# UPCNSL-ABS-PVC-2B.net
KiCad netlist of a schematic drawn in Altium Designer
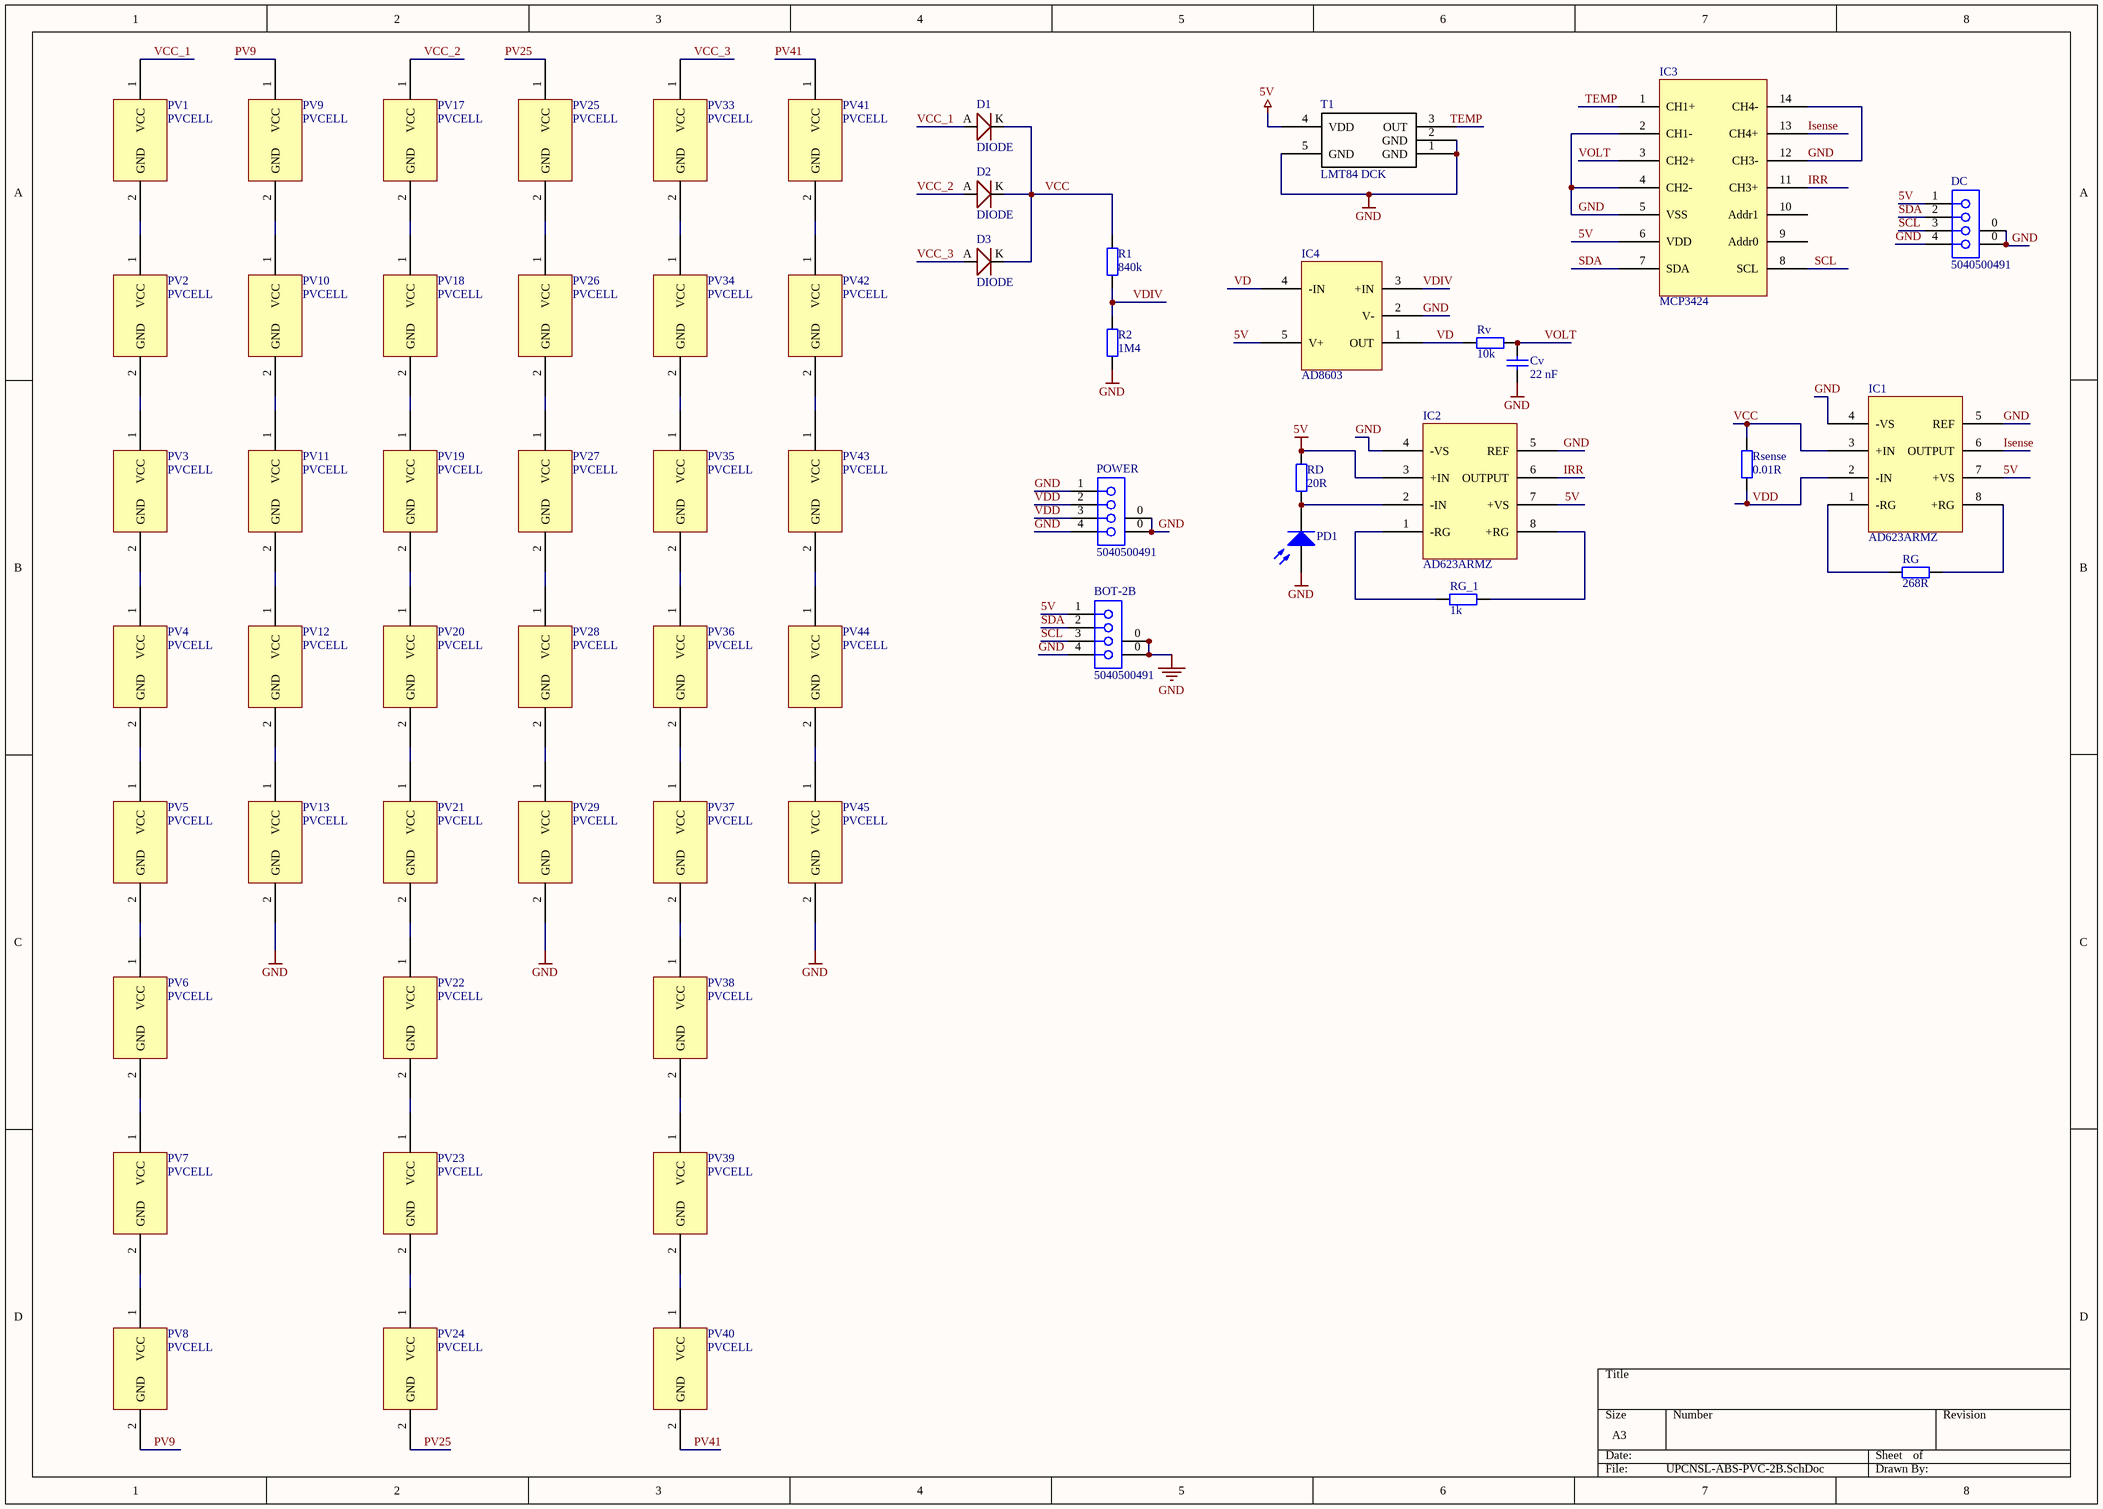
[diagram p0: UPCNSL-ABS-PVC-2B.SchDoc]

(export (version "E")
  (design (tool "Eeschema 10.0.6"))
  (components
    (comp (ref "BOT-2B")
      (value "5040500491")
      (footprint "5040500491")
      (libsource (lib "3CAT_Connectors") (part "MOLEX_5040500491"))
    )
    (comp (ref "Cv")
      (value "22 nF")
      (footprint "CAP0603")
      (description "Capacitor")
      (fields (field (name "Comment") "CAP0603"))
      (libsource (lib "UPCNSL-ABS-FLS-ARD_v1.2") (part "CAP0603"))
    )
    (comp (ref "D1")
      (value "DIODE")
      (footprint "(Schottky diode) SODFL160X70-2N")
      (libsource (lib "UPCNSL-ABS-FLS-ARD_v1.2") (part "DIODE"))
    )
    (comp (ref "D2")
      (value "DIODE")
      (footprint "(Schottky diode) SODFL160X70-2N")
      (libsource (lib "UPCNSL-ABS-FLS-ARD_v1.2") (part "DIODE"))
    )
    (comp (ref "D3")
      (value "DIODE")
      (footprint "(Schottky diode) SODFL160X70-2N")
      (libsource (lib "UPCNSL-ABS-FLS-ARD_v1.2") (part "DIODE"))
    )
    (comp (ref "DC")
      (value "5040500491")
      (footprint "5040500491")
      (libsource (lib "3CAT_Connectors") (part "MOLEX_5040500491"))
    )
    (comp (ref "IC1")
      (value "AD623ARMZ")
      (footprint "AD623ARMZ")
      (libsource (lib "UPCNSL-ABS-FLS-PVC") (part "AD623ARMZ"))
    )
    (comp (ref "IC2")
      (value "AD623ARMZ")
      (footprint "AD623ARMZ")
      (libsource (lib "UPCNSL-ABS-FLS-PVC") (part "AD623ARMZ"))
    )
    (comp (ref "IC3")
      (value "MCP3424")
      (footprint "MCP3424")
      (description "18-Bit, Multi-Channel ΔΣ Analog-to-Digital Converter with  I2C")
      (libsource (lib "UPCNSL-ABS-FLS-PVC") (part "MCP3424"))
    )
    (comp (ref "IC4")
      (value "AD8603")
      (footprint "AD8603")
      (libsource (lib "UPCNSL-ABS-FLS-PVC") (part "AD8603"))
    )
    (comp (ref "PD1")
      (value "Photo Sen")
      (footprint "C0805")
      (description "Photosensitive Diode")
      (fields (field (name "PUBLISHER") "Altium Limited"))
      (libsource (lib "Miscellaneous Devices") (part "Photo Sen"))
    )
    (comp (ref "POWER")
      (value "5040500491")
      (footprint "5040500491")
      (libsource (lib "3CAT_Connectors") (part "MOLEX_5040500491"))
    )
    (comp (ref "PV1")
      (value "PVCELL")
      (footprint "PV CELLS")
      (description "IXYS KXOB22-12X1L-ND")
      (libsource (lib "UPCNSL-ABS-FLS-PVC") (part "PVCELLS"))
    )
    (comp (ref "PV2")
      (value "PVCELL")
      (footprint "PV CELLS")
      (description "IXYS KXOB22-12X1L-ND")
      (libsource (lib "UPCNSL-ABS-FLS-PVC") (part "PVCELLS"))
    )
    (comp (ref "PV3")
      (value "PVCELL")
      (footprint "PV CELLS")
      (description "IXYS KXOB22-12X1L-ND")
      (libsource (lib "UPCNSL-ABS-FLS-PVC") (part "PVCELLS"))
    )
    (comp (ref "PV4")
      (value "PVCELL")
      (footprint "PV CELLS")
      (description "IXYS KXOB22-12X1L-ND")
      (libsource (lib "UPCNSL-ABS-FLS-PVC") (part "PVCELLS"))
    )
    (comp (ref "PV5")
      (value "PVCELL")
      (footprint "PV CELLS")
      (description "IXYS KXOB22-12X1L-ND")
      (libsource (lib "UPCNSL-ABS-FLS-PVC") (part "PVCELLS"))
    )
    (comp (ref "PV6")
      (value "PVCELL")
      (footprint "PV CELLS")
      (description "IXYS KXOB22-12X1L-ND")
      (libsource (lib "UPCNSL-ABS-FLS-PVC") (part "PVCELLS"))
    )
    (comp (ref "PV7")
      (value "PVCELL")
      (footprint "PV CELLS")
      (description "IXYS KXOB22-12X1L-ND")
      (libsource (lib "UPCNSL-ABS-FLS-PVC") (part "PVCELLS"))
    )
    (comp (ref "PV8")
      (value "PVCELL")
      (footprint "PV CELLS")
      (description "IXYS KXOB22-12X1L-ND")
      (libsource (lib "UPCNSL-ABS-FLS-PVC") (part "PVCELLS"))
    )
    (comp (ref "PV9")
      (value "PVCELL")
      (footprint "PV CELLS")
      (description "IXYS KXOB22-12X1L-ND")
      (libsource (lib "UPCNSL-ABS-FLS-PVC") (part "PVCELLS"))
    )
    (comp (ref "PV10")
      (value "PVCELL")
      (footprint "PV CELLS")
      (description "IXYS KXOB22-12X1L-ND")
      (libsource (lib "UPCNSL-ABS-FLS-PVC") (part "PVCELLS"))
    )
    (comp (ref "PV11")
      (value "PVCELL")
      (footprint "PV CELLS")
      (description "IXYS KXOB22-12X1L-ND")
      (libsource (lib "UPCNSL-ABS-FLS-PVC") (part "PVCELLS"))
    )
    (comp (ref "PV12")
      (value "PVCELL")
      (footprint "PV CELLS")
      (description "IXYS KXOB22-12X1L-ND")
      (libsource (lib "UPCNSL-ABS-FLS-PVC") (part "PVCELLS"))
    )
    (comp (ref "PV13")
      (value "PVCELL")
      (footprint "PV CELLS")
      (description "IXYS KXOB22-12X1L-ND")
      (libsource (lib "UPCNSL-ABS-FLS-PVC") (part "PVCELLS"))
    )
    (comp (ref "PV17")
      (value "PVCELL")
      (footprint "PV CELLS")
      (description "IXYS KXOB22-12X1L-ND")
      (libsource (lib "UPCNSL-ABS-FLS-PVC") (part "PVCELLS"))
    )
    (comp (ref "PV18")
      (value "PVCELL")
      (footprint "PV CELLS")
      (description "IXYS KXOB22-12X1L-ND")
      (libsource (lib "UPCNSL-ABS-FLS-PVC") (part "PVCELLS"))
    )
    (comp (ref "PV19")
      (value "PVCELL")
      (footprint "PV CELLS")
      (description "IXYS KXOB22-12X1L-ND")
      (libsource (lib "UPCNSL-ABS-FLS-PVC") (part "PVCELLS"))
    )
    (comp (ref "PV20")
      (value "PVCELL")
      (footprint "PV CELLS")
      (description "IXYS KXOB22-12X1L-ND")
      (libsource (lib "UPCNSL-ABS-FLS-PVC") (part "PVCELLS"))
    )
    (comp (ref "PV21")
      (value "PVCELL")
      (footprint "PV CELLS")
      (description "IXYS KXOB22-12X1L-ND")
      (libsource (lib "UPCNSL-ABS-FLS-PVC") (part "PVCELLS"))
    )
    (comp (ref "PV22")
      (value "PVCELL")
      (footprint "PV CELLS")
      (description "IXYS KXOB22-12X1L-ND")
      (libsource (lib "UPCNSL-ABS-FLS-PVC") (part "PVCELLS"))
    )
    (comp (ref "PV23")
      (value "PVCELL")
      (footprint "PV CELLS")
      (description "IXYS KXOB22-12X1L-ND")
      (libsource (lib "UPCNSL-ABS-FLS-PVC") (part "PVCELLS"))
    )
    (comp (ref "PV24")
      (value "PVCELL")
      (footprint "PV CELLS")
      (description "IXYS KXOB22-12X1L-ND")
      (libsource (lib "UPCNSL-ABS-FLS-PVC") (part "PVCELLS"))
    )
    (comp (ref "PV25")
      (value "PVCELL")
      (footprint "PV CELLS")
      (description "IXYS KXOB22-12X1L-ND")
      (libsource (lib "UPCNSL-ABS-FLS-PVC") (part "PVCELLS"))
    )
    (comp (ref "PV26")
      (value "PVCELL")
      (footprint "PV CELLS")
      (description "IXYS KXOB22-12X1L-ND")
      (libsource (lib "UPCNSL-ABS-FLS-PVC") (part "PVCELLS"))
    )
    (comp (ref "PV27")
      (value "PVCELL")
      (footprint "PV CELLS")
      (description "IXYS KXOB22-12X1L-ND")
      (libsource (lib "UPCNSL-ABS-FLS-PVC") (part "PVCELLS"))
    )
    (comp (ref "PV28")
      (value "PVCELL")
      (footprint "PV CELLS")
      (description "IXYS KXOB22-12X1L-ND")
      (libsource (lib "UPCNSL-ABS-FLS-PVC") (part "PVCELLS"))
    )
    (comp (ref "PV29")
      (value "PVCELL")
      (footprint "PV CELLS")
      (description "IXYS KXOB22-12X1L-ND")
      (libsource (lib "UPCNSL-ABS-FLS-PVC") (part "PVCELLS"))
    )
    (comp (ref "PV33")
      (value "PVCELL")
      (footprint "PV CELLS")
      (description "IXYS KXOB22-12X1L-ND")
      (libsource (lib "UPCNSL-ABS-FLS-PVC") (part "PVCELLS"))
    )
    (comp (ref "PV34")
      (value "PVCELL")
      (footprint "PV CELLS")
      (description "IXYS KXOB22-12X1L-ND")
      (libsource (lib "UPCNSL-ABS-FLS-PVC") (part "PVCELLS"))
    )
    (comp (ref "PV35")
      (value "PVCELL")
      (footprint "PV CELLS")
      (description "IXYS KXOB22-12X1L-ND")
      (libsource (lib "UPCNSL-ABS-FLS-PVC") (part "PVCELLS"))
    )
    (comp (ref "PV36")
      (value "PVCELL")
      (footprint "PV CELLS")
      (description "IXYS KXOB22-12X1L-ND")
      (libsource (lib "UPCNSL-ABS-FLS-PVC") (part "PVCELLS"))
    )
    (comp (ref "PV37")
      (value "PVCELL")
      (footprint "PV CELLS")
      (description "IXYS KXOB22-12X1L-ND")
      (libsource (lib "UPCNSL-ABS-FLS-PVC") (part "PVCELLS"))
    )
    (comp (ref "PV38")
      (value "PVCELL")
      (footprint "PV CELLS")
      (description "IXYS KXOB22-12X1L-ND")
      (libsource (lib "UPCNSL-ABS-FLS-PVC") (part "PVCELLS"))
    )
    (comp (ref "PV39")
      (value "PVCELL")
      (footprint "PV CELLS")
      (description "IXYS KXOB22-12X1L-ND")
      (libsource (lib "UPCNSL-ABS-FLS-PVC") (part "PVCELLS"))
    )
    (comp (ref "PV40")
      (value "PVCELL")
      (footprint "PV CELLS")
      (description "IXYS KXOB22-12X1L-ND")
      (libsource (lib "UPCNSL-ABS-FLS-PVC") (part "PVCELLS"))
    )
    (comp (ref "PV41")
      (value "PVCELL")
      (footprint "PV CELLS")
      (description "IXYS KXOB22-12X1L-ND")
      (libsource (lib "UPCNSL-ABS-FLS-PVC") (part "PVCELLS"))
    )
    (comp (ref "PV42")
      (value "PVCELL")
      (footprint "PV CELLS")
      (description "IXYS KXOB22-12X1L-ND")
      (libsource (lib "UPCNSL-ABS-FLS-PVC") (part "PVCELLS"))
    )
    (comp (ref "PV43")
      (value "PVCELL")
      (footprint "PV CELLS")
      (description "IXYS KXOB22-12X1L-ND")
      (libsource (lib "UPCNSL-ABS-FLS-PVC") (part "PVCELLS"))
    )
    (comp (ref "PV44")
      (value "PVCELL")
      (footprint "PV CELLS")
      (description "IXYS KXOB22-12X1L-ND")
      (libsource (lib "UPCNSL-ABS-FLS-PVC") (part "PVCELLS"))
    )
    (comp (ref "PV45")
      (value "PVCELL")
      (footprint "PV CELLS")
      (description "IXYS KXOB22-12X1L-ND")
      (libsource (lib "UPCNSL-ABS-FLS-PVC") (part "PVCELLS"))
    )
    (comp (ref "R1")
      (value "840k")
      (footprint "RES0603")
      (description "Resistor")
      (fields (field (name "Comment") "RES0603"))
      (libsource (lib "UPCNSL-ABS-FLS-ARD_v1.2") (part "RES0603"))
    )
    (comp (ref "R2")
      (value "1M4")
      (footprint "RES0603")
      (description "Resistor")
      (fields (field (name "Comment") "RES0603"))
      (libsource (lib "UPCNSL-ABS-FLS-ARD_v1.2") (part "RES0603"))
    )
    (comp (ref "RD")
      (value "20R")
      (footprint "RES0603")
      (description "Resistor")
      (fields (field (name "Comment") "RES0603"))
      (libsource (lib "UPCNSL-ABS-FLS-ARD_v1.2") (part "RES0603"))
    )
    (comp (ref "RG")
      (value "268R")
      (footprint "RES0603")
      (description "Resistor")
      (fields (field (name "Comment") "RES0603"))
      (libsource (lib "") (part "RES0603_1"))
    )
    (comp (ref "RG_1")
      (value "1k")
      (footprint "RES0603")
      (description "Resistor")
      (fields (field (name "Comment") "RES0603"))
      (libsource (lib "") (part "RES0603_1"))
    )
    (comp (ref "Rsense")
      (value "0.01R")
      (footprint "RES0603")
      (description "Resistor")
      (fields (field (name "Comment") "RES0603"))
      (libsource (lib "UPCNSL-ABS-FLS-ARD_v1.2") (part "RES0603"))
    )
    (comp (ref "Rv")
      (value "10k")
      (footprint "RES0603")
      (description "Resistor")
      (fields (field (name "Comment") "RES0603"))
      (libsource (lib "") (part "RES0603_1"))
    )
    (comp (ref "T1")
      (value "LMT84 DCK")
      (footprint "DCK/SOT65P210X110-5N")
      (libsource (lib "UPCNSL-ABS-FLS-PVC") (part "LMT84 DCK"))
    )
  )
  (nets
    (net (code "1") (name "/IRR") (class "Default")
      (node (ref "IC2") (pin "6") (pinfunction "OUTPUT_6") (pintype "passive"))
      (node (ref "IC3") (pin "11") (pinfunction "CH3+_11") (pintype "passive"))
    )
    (net (code "2") (name "/Isense") (class "Default")
      (node (ref "IC1") (pin "6") (pinfunction "OUTPUT_6") (pintype "passive"))
      (node (ref "IC3") (pin "13") (pinfunction "CH4+_13") (pintype "passive"))
    )
    (net (code "3") (name "/PV9") (class "Default")
      (node (ref "PV8") (pin "2") (pinfunction "GND_2") (pintype "passive"))
      (node (ref "PV9") (pin "1") (pinfunction "VCC_1") (pintype "passive"))
    )
    (net (code "4") (name "/PV25") (class "Default")
      (node (ref "PV24") (pin "2") (pinfunction "GND_2") (pintype "passive"))
      (node (ref "PV25") (pin "1") (pinfunction "VCC_1") (pintype "passive"))
    )
    (net (code "5") (name "/PV41") (class "Default")
      (node (ref "PV40") (pin "2") (pinfunction "GND_2") (pintype "passive"))
      (node (ref "PV41") (pin "1") (pinfunction "VCC_1") (pintype "passive"))
    )
    (net (code "6") (name "/SCL") (class "Default")
      (node (ref "BOT-2B") (pin "3") (pinfunction "3_3") (pintype "passive"))
      (node (ref "DC") (pin "3") (pinfunction "3_3") (pintype "passive"))
      (node (ref "IC3") (pin "8") (pinfunction "SCL_8") (pintype "passive"))
    )
    (net (code "7") (name "/SDA") (class "Default")
      (node (ref "BOT-2B") (pin "2") (pinfunction "2_2") (pintype "passive"))
      (node (ref "DC") (pin "2") (pinfunction "2_2") (pintype "passive"))
      (node (ref "IC3") (pin "7") (pinfunction "SDA_7") (pintype "passive"))
    )
    (net (code "8") (name "/TEMP") (class "Default")
      (node (ref "IC3") (pin "1") (pinfunction "CH1+_1") (pintype "passive"))
    )
    (net (code "9") (name "/VCC") (class "Default")
      (node (ref "D1") (pin "K") (pinfunction "K_K") (pintype "passive"))
      (node (ref "D2") (pin "K") (pinfunction "K_K") (pintype "passive"))
      (node (ref "D3") (pin "K") (pinfunction "K_K") (pintype "passive"))
      (node (ref "IC1") (pin "3") (pinfunction "+IN_3") (pintype "passive"))
      (node (ref "R1") (pin "2") (pinfunction "2_2") (pintype "passive"))
      (node (ref "Rsense") (pin "2") (pinfunction "2_2") (pintype "passive"))
    )
    (net (code "10") (name "/VCC_1") (class "Default")
      (node (ref "D1") (pin "A") (pinfunction "A_A") (pintype "passive"))
      (node (ref "PV1") (pin "1") (pinfunction "VCC_1") (pintype "passive"))
    )
    (net (code "11") (name "/VCC_2") (class "Default")
      (node (ref "D2") (pin "A") (pinfunction "A_A") (pintype "passive"))
      (node (ref "PV17") (pin "1") (pinfunction "VCC_1") (pintype "passive"))
    )
    (net (code "12") (name "/VCC_3") (class "Default")
      (node (ref "D3") (pin "A") (pinfunction "A_A") (pintype "passive"))
      (node (ref "PV33") (pin "1") (pinfunction "VCC_1") (pintype "passive"))
    )
    (net (code "13") (name "/VD") (class "Default")
      (node (ref "IC4") (pin "1") (pinfunction "OUT_1") (pintype "passive"))
      (node (ref "IC4") (pin "4") (pinfunction "-IN_4") (pintype "passive"))
      (node (ref "Rv") (pin "1") (pinfunction "1_1") (pintype "passive"))
    )
    (net (code "14") (name "/VDD") (class "Default")
      (node (ref "IC1") (pin "2") (pinfunction "-IN_2") (pintype "passive"))
      (node (ref "POWER") (pin "2") (pinfunction "2_2") (pintype "passive"))
      (node (ref "POWER") (pin "3") (pinfunction "3_3") (pintype "passive"))
      (node (ref "Rsense") (pin "1") (pinfunction "1_1") (pintype "passive"))
    )
    (net (code "15") (name "/VDIV") (class "Default")
      (node (ref "IC4") (pin "3") (pinfunction "+IN_3") (pintype "passive"))
      (node (ref "R1") (pin "1") (pinfunction "1_1") (pintype "passive"))
      (node (ref "R2") (pin "2") (pinfunction "2_2") (pintype "passive"))
    )
    (net (code "16") (name "/VOLT") (class "Default")
      (node (ref "Cv") (pin "2") (pinfunction "2_2") (pintype "passive"))
      (node (ref "IC3") (pin "3") (pinfunction "CH2+_3") (pintype "passive"))
      (node (ref "Rv") (pin "2") (pinfunction "2_2") (pintype "passive"))
    )
    (net (code "17") (name "5V") (class "Default")
      (node (ref "BOT-2B") (pin "1") (pinfunction "1_1") (pintype "passive"))
      (node (ref "DC") (pin "1") (pinfunction "1_1") (pintype "passive"))
      (node (ref "IC1") (pin "7") (pinfunction "+VS_7") (pintype "passive"))
      (node (ref "IC2") (pin "3") (pinfunction "+IN_3") (pintype "passive"))
      (node (ref "IC2") (pin "7") (pinfunction "+VS_7") (pintype "passive"))
      (node (ref "IC3") (pin "6") (pinfunction "VDD_6") (pintype "passive"))
      (node (ref "IC4") (pin "5") (pinfunction "V+_5") (pintype "passive"))
      (node (ref "RD") (pin "2") (pinfunction "2_2") (pintype "passive"))
      (node (ref "T1") (pin "4") (pinfunction "VDD_4") (pintype "passive"))
    )
    (net (code "18") (name "GND") (class "Default")
      (node (ref "BOT-2B") (pin "0") (pinfunction "MH1_0") (pintype "passive"))
      (node (ref "BOT-2B") (pin "4") (pinfunction "4_4") (pintype "passive"))
      (node (ref "Cv") (pin "1") (pinfunction "1_1") (pintype "passive"))
      (node (ref "DC") (pin "0") (pinfunction "MH1_0") (pintype "passive"))
      (node (ref "DC") (pin "4") (pinfunction "4_4") (pintype "passive"))
      (node (ref "IC1") (pin "4") (pinfunction "-VS_4") (pintype "passive"))
      (node (ref "IC1") (pin "5") (pinfunction "REF_5") (pintype "passive"))
      (node (ref "IC2") (pin "4") (pinfunction "-VS_4") (pintype "passive"))
      (node (ref "IC2") (pin "5") (pinfunction "REF_5") (pintype "passive"))
      (node (ref "IC3") (pin "12") (pinfunction "CH3-_12") (pintype "passive"))
      (node (ref "IC3") (pin "14") (pinfunction "CH4-_14") (pintype "passive"))
      (node (ref "IC3") (pin "2") (pinfunction "CH1-_2") (pintype "passive"))
      (node (ref "IC3") (pin "4") (pinfunction "CH2-_4") (pintype "passive"))
      (node (ref "IC3") (pin "5") (pinfunction "VSS_5") (pintype "passive"))
      (node (ref "IC4") (pin "2") (pinfunction "V-_2") (pintype "passive"))
      (node (ref "PD1") (pin "1") (pinfunction "A_1") (pintype "passive"))
      (node (ref "POWER") (pin "0") (pinfunction "MH1_0") (pintype "passive"))
      (node (ref "POWER") (pin "1") (pinfunction "1_1") (pintype "passive"))
      (node (ref "POWER") (pin "4") (pinfunction "4_4") (pintype "passive"))
      (node (ref "PV13") (pin "2") (pinfunction "GND_2") (pintype "passive"))
      (node (ref "PV29") (pin "2") (pinfunction "GND_2") (pintype "passive"))
      (node (ref "PV45") (pin "2") (pinfunction "GND_2") (pintype "passive"))
      (node (ref "R2") (pin "1") (pinfunction "1_1") (pintype "passive"))
      (node (ref "T1") (pin "1") (pinfunction "GND_1") (pintype "passive"))
      (node (ref "T1") (pin "2") (pinfunction "GND_2") (pintype "passive"))
      (node (ref "T1") (pin "5") (pinfunction "GND_5") (pintype "passive"))
    )
    (net (code "19") (name "Net-(IC1-+RG)") (class "Default")
      (node (ref "IC1") (pin "8") (pinfunction "+RG_8") (pintype "passive"))
      (node (ref "RG") (pin "2") (pinfunction "2_2") (pintype "passive"))
    )
    (net (code "20") (name "Net-(IC1--RG)") (class "Default")
      (node (ref "IC1") (pin "1") (pinfunction "-RG_1") (pintype "passive"))
      (node (ref "RG") (pin "1") (pinfunction "1_1") (pintype "passive"))
    )
    (net (code "21") (name "Net-(IC2-+RG)") (class "Default")
      (node (ref "IC2") (pin "8") (pinfunction "+RG_8") (pintype "passive"))
      (node (ref "RG_1") (pin "2") (pinfunction "2_2") (pintype "passive"))
    )
    (net (code "22") (name "Net-(IC2--IN)") (class "Default")
      (node (ref "IC2") (pin "2") (pinfunction "-IN_2") (pintype "passive"))
      (node (ref "PD1") (pin "2") (pinfunction "K_2") (pintype "passive"))
      (node (ref "RD") (pin "1") (pinfunction "1_1") (pintype "passive"))
    )
    (net (code "23") (name "Net-(IC2--RG)") (class "Default")
      (node (ref "IC2") (pin "1") (pinfunction "-RG_1") (pintype "passive"))
      (node (ref "RG_1") (pin "1") (pinfunction "1_1") (pintype "passive"))
    )
    (net (code "24") (name "Net-(PV1-GND)") (class "Default")
      (node (ref "PV1") (pin "2") (pinfunction "GND_2") (pintype "passive"))
      (node (ref "PV2") (pin "1") (pinfunction "VCC_1") (pintype "passive"))
    )
    (net (code "25") (name "Net-(PV2-GND)") (class "Default")
      (node (ref "PV2") (pin "2") (pinfunction "GND_2") (pintype "passive"))
      (node (ref "PV3") (pin "1") (pinfunction "VCC_1") (pintype "passive"))
    )
    (net (code "26") (name "Net-(PV3-GND)") (class "Default")
      (node (ref "PV3") (pin "2") (pinfunction "GND_2") (pintype "passive"))
      (node (ref "PV4") (pin "1") (pinfunction "VCC_1") (pintype "passive"))
    )
    (net (code "27") (name "Net-(PV4-GND)") (class "Default")
      (node (ref "PV4") (pin "2") (pinfunction "GND_2") (pintype "passive"))
      (node (ref "PV5") (pin "1") (pinfunction "VCC_1") (pintype "passive"))
    )
    (net (code "28") (name "Net-(PV5-GND)") (class "Default")
      (node (ref "PV5") (pin "2") (pinfunction "GND_2") (pintype "passive"))
      (node (ref "PV6") (pin "1") (pinfunction "VCC_1") (pintype "passive"))
    )
    (net (code "29") (name "Net-(PV6-GND)") (class "Default")
      (node (ref "PV6") (pin "2") (pinfunction "GND_2") (pintype "passive"))
      (node (ref "PV7") (pin "1") (pinfunction "VCC_1") (pintype "passive"))
    )
    (net (code "30") (name "Net-(PV7-GND)") (class "Default")
      (node (ref "PV7") (pin "2") (pinfunction "GND_2") (pintype "passive"))
      (node (ref "PV8") (pin "1") (pinfunction "VCC_1") (pintype "passive"))
    )
    (net (code "31") (name "Net-(PV10-GND)") (class "Default")
      (node (ref "PV10") (pin "2") (pinfunction "GND_2") (pintype "passive"))
      (node (ref "PV11") (pin "1") (pinfunction "VCC_1") (pintype "passive"))
    )
    (net (code "32") (name "Net-(PV10-VCC)") (class "Default")
      (node (ref "PV10") (pin "1") (pinfunction "VCC_1") (pintype "passive"))
      (node (ref "PV9") (pin "2") (pinfunction "GND_2") (pintype "passive"))
    )
    (net (code "33") (name "Net-(PV11-GND)") (class "Default")
      (node (ref "PV11") (pin "2") (pinfunction "GND_2") (pintype "passive"))
      (node (ref "PV12") (pin "1") (pinfunction "VCC_1") (pintype "passive"))
    )
    (net (code "34") (name "Net-(PV12-GND)") (class "Default")
      (node (ref "PV12") (pin "2") (pinfunction "GND_2") (pintype "passive"))
      (node (ref "PV13") (pin "1") (pinfunction "VCC_1") (pintype "passive"))
    )
    (net (code "35") (name "Net-(PV17-GND)") (class "Default")
      (node (ref "PV17") (pin "2") (pinfunction "GND_2") (pintype "passive"))
      (node (ref "PV18") (pin "1") (pinfunction "VCC_1") (pintype "passive"))
    )
    (net (code "36") (name "Net-(PV18-GND)") (class "Default")
      (node (ref "PV18") (pin "2") (pinfunction "GND_2") (pintype "passive"))
      (node (ref "PV19") (pin "1") (pinfunction "VCC_1") (pintype "passive"))
    )
    (net (code "37") (name "Net-(PV19-GND)") (class "Default")
      (node (ref "PV19") (pin "2") (pinfunction "GND_2") (pintype "passive"))
      (node (ref "PV20") (pin "1") (pinfunction "VCC_1") (pintype "passive"))
    )
    (net (code "38") (name "Net-(PV20-GND)") (class "Default")
      (node (ref "PV20") (pin "2") (pinfunction "GND_2") (pintype "passive"))
      (node (ref "PV21") (pin "1") (pinfunction "VCC_1") (pintype "passive"))
    )
    (net (code "39") (name "Net-(PV21-GND)") (class "Default")
      (node (ref "PV21") (pin "2") (pinfunction "GND_2") (pintype "passive"))
      (node (ref "PV22") (pin "1") (pinfunction "VCC_1") (pintype "passive"))
    )
    (net (code "40") (name "Net-(PV22-GND)") (class "Default")
      (node (ref "PV22") (pin "2") (pinfunction "GND_2") (pintype "passive"))
      (node (ref "PV23") (pin "1") (pinfunction "VCC_1") (pintype "passive"))
    )
    (net (code "41") (name "Net-(PV23-GND)") (class "Default")
      (node (ref "PV23") (pin "2") (pinfunction "GND_2") (pintype "passive"))
      (node (ref "PV24") (pin "1") (pinfunction "VCC_1") (pintype "passive"))
    )
    (net (code "42") (name "Net-(PV25-GND)") (class "Default")
      (node (ref "PV25") (pin "2") (pinfunction "GND_2") (pintype "passive"))
      (node (ref "PV26") (pin "1") (pinfunction "VCC_1") (pintype "passive"))
    )
    (net (code "43") (name "Net-(PV26-GND)") (class "Default")
      (node (ref "PV26") (pin "2") (pinfunction "GND_2") (pintype "passive"))
      (node (ref "PV27") (pin "1") (pinfunction "VCC_1") (pintype "passive"))
    )
    (net (code "44") (name "Net-(PV27-GND)") (class "Default")
      (node (ref "PV27") (pin "2") (pinfunction "GND_2") (pintype "passive"))
      (node (ref "PV28") (pin "1") (pinfunction "VCC_1") (pintype "passive"))
    )
    (net (code "45") (name "Net-(PV28-GND)") (class "Default")
      (node (ref "PV28") (pin "2") (pinfunction "GND_2") (pintype "passive"))
      (node (ref "PV29") (pin "1") (pinfunction "VCC_1") (pintype "passive"))
    )
    (net (code "46") (name "Net-(PV33-GND)") (class "Default")
      (node (ref "PV33") (pin "2") (pinfunction "GND_2") (pintype "passive"))
      (node (ref "PV34") (pin "1") (pinfunction "VCC_1") (pintype "passive"))
    )
    (net (code "47") (name "Net-(PV34-GND)") (class "Default")
      (node (ref "PV34") (pin "2") (pinfunction "GND_2") (pintype "passive"))
      (node (ref "PV35") (pin "1") (pinfunction "VCC_1") (pintype "passive"))
    )
    (net (code "48") (name "Net-(PV35-GND)") (class "Default")
      (node (ref "PV35") (pin "2") (pinfunction "GND_2") (pintype "passive"))
      (node (ref "PV36") (pin "1") (pinfunction "VCC_1") (pintype "passive"))
    )
    (net (code "49") (name "Net-(PV36-GND)") (class "Default")
      (node (ref "PV36") (pin "2") (pinfunction "GND_2") (pintype "passive"))
      (node (ref "PV37") (pin "1") (pinfunction "VCC_1") (pintype "passive"))
    )
    (net (code "50") (name "Net-(PV37-GND)") (class "Default")
      (node (ref "PV37") (pin "2") (pinfunction "GND_2") (pintype "passive"))
      (node (ref "PV38") (pin "1") (pinfunction "VCC_1") (pintype "passive"))
    )
    (net (code "51") (name "Net-(PV38-GND)") (class "Default")
      (node (ref "PV38") (pin "2") (pinfunction "GND_2") (pintype "passive"))
      (node (ref "PV39") (pin "1") (pinfunction "VCC_1") (pintype "passive"))
    )
    (net (code "52") (name "Net-(PV39-GND)") (class "Default")
      (node (ref "PV39") (pin "2") (pinfunction "GND_2") (pintype "passive"))
      (node (ref "PV40") (pin "1") (pinfunction "VCC_1") (pintype "passive"))
    )
    (net (code "53") (name "Net-(PV41-GND)") (class "Default")
      (node (ref "PV41") (pin "2") (pinfunction "GND_2") (pintype "passive"))
      (node (ref "PV42") (pin "1") (pinfunction "VCC_1") (pintype "passive"))
    )
    (net (code "54") (name "Net-(PV42-GND)") (class "Default")
      (node (ref "PV42") (pin "2") (pinfunction "GND_2") (pintype "passive"))
      (node (ref "PV43") (pin "1") (pinfunction "VCC_1") (pintype "passive"))
    )
    (net (code "55") (name "Net-(PV43-GND)") (class "Default")
      (node (ref "PV43") (pin "2") (pinfunction "GND_2") (pintype "passive"))
      (node (ref "PV44") (pin "1") (pinfunction "VCC_1") (pintype "passive"))
    )
    (net (code "56") (name "Net-(PV44-GND)") (class "Default")
      (node (ref "PV44") (pin "2") (pinfunction "GND_2") (pintype "passive"))
      (node (ref "PV45") (pin "1") (pinfunction "VCC_1") (pintype "passive"))
    )
    (net (code "57") (name "unconnected-(IC3-Addr0-Pad9)") (class "Default")
      (node (ref "IC3") (pin "9") (pinfunction "Addr0_9") (pintype "passive"))
    )
    (net (code "58") (name "unconnected-(IC3-Addr1-Pad10)") (class "Default")
      (node (ref "IC3") (pin "10") (pinfunction "Addr1_10") (pintype "passive"))
    )
    (net (code "59") (name "unconnected-(T1-OUT-Pad3)") (class "Default")
      (node (ref "T1") (pin "3") (pinfunction "OUT_3") (pintype "passive"))
    )
  )
)
